# PROFIBUS_V5.net
KiCad netlist of a schematic drawn in EAGLE
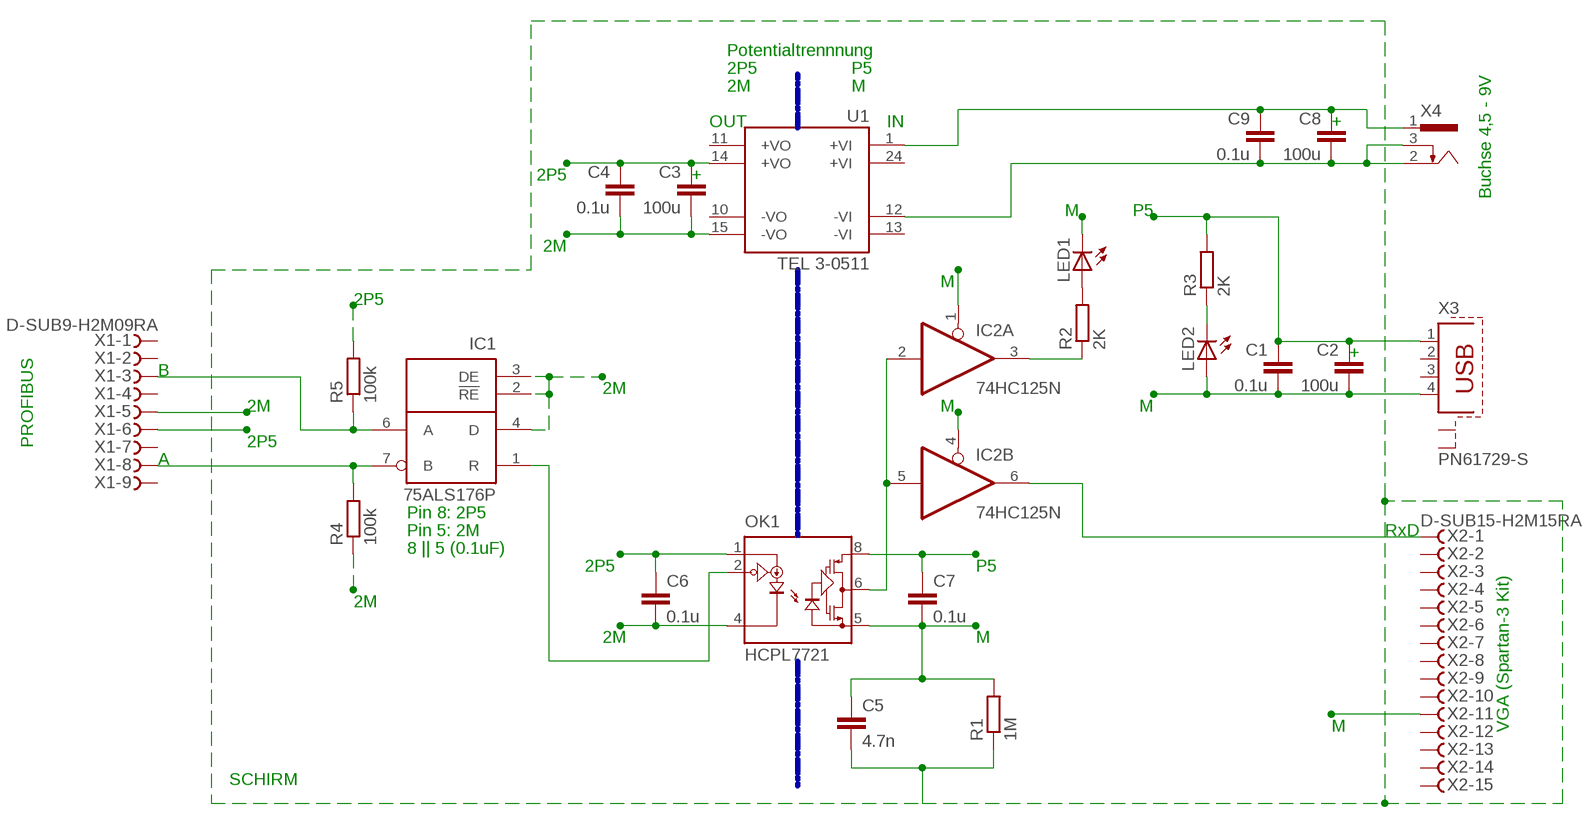
[diagram p0: schematic, sheet 1]

(export (version "E")
  (design (tool "Eeschema 10.0.6"))
  (components
    (comp (ref "C1")
      (value "0.1u")
      (footprint "eagle-import:C2.5-3")
      (libsource (lib "eagle-import") (part "C2,5-3"))
    )
    (comp (ref "C2")
      (value "100u")
      (footprint "eagle-import:C2.5-3")
      (libsource (lib "eagle-import") (part "C2,5-3"))
    )
    (comp (ref "C3")
      (value "100u")
      (footprint "eagle-import:C2.5-3")
      (libsource (lib "eagle-import") (part "C2,5-3"))
    )
    (comp (ref "C4")
      (value "0.1u")
      (footprint "eagle-import:C2.5-3")
      (libsource (lib "eagle-import") (part "C2,5-3"))
    )
    (comp (ref "C5")
      (value "4.7n")
      (footprint "eagle-import:C2.5-3")
      (libsource (lib "eagle-import") (part "C2,5-3"))
    )
    (comp (ref "C6")
      (value "0.1u")
      (footprint "eagle-import:C2.5-3")
      (libsource (lib "eagle-import") (part "C2,5-3"))
    )
    (comp (ref "C7")
      (value "0.1u")
      (footprint "eagle-import:C2.5-3")
      (libsource (lib "eagle-import") (part "C2,5-3"))
    )
    (comp (ref "C8")
      (value "100u")
      (footprint "eagle-import:C2.5-3")
      (libsource (lib "eagle-import") (part "C2,5-3"))
    )
    (comp (ref "C9")
      (value "0.1u")
      (footprint "eagle-import:C2.5-3")
      (libsource (lib "eagle-import") (part "C2,5-3"))
    )
    (comp (ref "IC1")
      (value "75ALS176P")
      (footprint "eagle-import:DIL08")
      (fields (field (name "MF") "TEXAS INSTRUMENTS") (field (name "MPN") "SN75ALS176P"))
      (libsource (lib "eagle-import") (part "75ALS176P"))
    )
    (comp (ref "IC2")
      (value "74HC125N")
      (footprint "eagle-import:DIL14")
      (libsource (lib "eagle-import") (part "74125NHC"))
    )
    (comp (ref "LED1")
      (value "TLLY4400")
      (footprint "eagle-import:LED3MM")
      (fields (field (name "MF") "VISHAY SEMICONDUCTOR"))
      (libsource (lib "eagle-import") (part "TLLY4400"))
    )
    (comp (ref "LED2")
      (value "TLLG4400")
      (footprint "eagle-import:LED3MM")
      (fields (field (name "MF") "VISHAY SEMICONDUCTOR"))
      (libsource (lib "eagle-import") (part "TLLG4400"))
    )
    (comp (ref "OK1")
      (value "HCPL7721")
      (footprint "eagle-import:DIL08")
      (fields (field (name "MF") "AGILENT TECHNOLOGIES") (field (name "MPN") "HCPL-7721"))
      (libsource (lib "eagle-import") (part "HCPL7721"))
    )
    (comp (ref "R1")
      (value "1M")
      (footprint "eagle-import:0204_7")
      (libsource (lib "eagle-import") (part "R-EU_0204/7"))
    )
    (comp (ref "R2")
      (value "2K")
      (footprint "eagle-import:0204_7")
      (libsource (lib "eagle-import") (part "R-EU_0204/7"))
    )
    (comp (ref "R3")
      (value "2K")
      (footprint "eagle-import:0204_7")
      (libsource (lib "eagle-import") (part "R-EU_0204/7"))
    )
    (comp (ref "R4")
      (value "100k")
      (footprint "eagle-import:0204_7")
      (libsource (lib "eagle-import") (part "R-EU_0204/7"))
    )
    (comp (ref "R5")
      (value "100k")
      (footprint "eagle-import:0204_7")
      (libsource (lib "eagle-import") (part "R-EU_0204/7"))
    )
    (comp (ref "U1")
      (value "TEL 3-0511")
      (footprint "eagle-import:AM3N_DIL24")
      (libsource (lib "eagle-import") (part "AM3N-S0505"))
    )
    (comp (ref "X1")
      (value "D-SUB9-H2M09RA")
      (footprint "eagle-import:H2M09RA")
      (libsource (lib "eagle-import") (part "D-SUB9-H2M09RA"))
    )
    (comp (ref "X2")
      (value "D-SUB15-H2M15RA")
      (footprint "eagle-import:H2M15RA")
      (fields (field (name "MPN") "H2M15RA29B"))
      (libsource (lib "eagle-import") (part "D-SUB15-H2M15RA"))
    )
    (comp (ref "X3")
      (value "PN61729-S")
      (footprint "eagle-import:PN61729-S")
      (libsource (lib "eagle-import") (part "PN61729-S"))
    )
    (comp (ref "X4")
      (value "733980-62")
      (footprint "eagle-import:733980-62")
      (libsource (lib "eagle-import") (part "73398?0-62"))
    )
  )
  (nets
    (net (code "1") (name "/+VI") (class "Default")
      (node (ref "U1") (pin "24") (pinfunction "+VI_24") (pintype "power_in"))
    )
    (net (code "2") (name "/+VO") (class "Default")
      (node (ref "U1") (pin "11") (pinfunction "+VO_11") (pintype "power_in"))
    )
    (net (code "3") (name "/-VI") (class "Default")
      (node (ref "U1") (pin "13") (pinfunction "-VI_13") (pintype "power_in"))
    )
    (net (code "4") (name "/-VO") (class "Default")
      (node (ref "U1") (pin "10") (pinfunction "-VO_10") (pintype "power_in"))
    )
    (net (code "5") (name "Net-(C1-Pad1)") (class "Default")
      (node (ref "C1") (pin "1") (pinfunction "1_1") (pintype "passive"))
      (node (ref "C2") (pin "1") (pinfunction "1_1") (pintype "passive"))
      (node (ref "R3") (pin "2") (pinfunction "2_2") (pintype "passive"))
      (node (ref "X3") (pin "1") (pinfunction "1_1") (pintype "passive"))
    )
    (net (code "6") (name "Net-(C1-Pad2)") (class "Default")
      (node (ref "C1") (pin "2") (pinfunction "2_2") (pintype "passive"))
      (node (ref "C2") (pin "2") (pinfunction "2_2") (pintype "passive"))
      (node (ref "LED2") (pin "A") (pinfunction "A_A") (pintype "passive"))
      (node (ref "X3") (pin "4") (pinfunction "4_4") (pintype "passive"))
    )
    (net (code "7") (name "Net-(C3-Pad1)") (class "Default")
      (node (ref "C3") (pin "1") (pinfunction "1_1") (pintype "passive"))
      (node (ref "C4") (pin "1") (pinfunction "1_1") (pintype "passive"))
      (node (ref "U1") (pin "14") (pinfunction "+VO_14") (pintype "power_in"))
    )
    (net (code "8") (name "Net-(C3-Pad2)") (class "Default")
      (node (ref "C3") (pin "2") (pinfunction "2_2") (pintype "passive"))
      (node (ref "C4") (pin "2") (pinfunction "2_2") (pintype "passive"))
      (node (ref "U1") (pin "15") (pinfunction "-VO_15") (pintype "power_in"))
    )
    (net (code "9") (name "Net-(C5-Pad2)") (class "Default")
      (node (ref "C5") (pin "2") (pinfunction "2_2") (pintype "passive"))
      (node (ref "R1") (pin "1") (pinfunction "1_1") (pintype "passive"))
    )
    (net (code "10") (name "Net-(C8-Pad1)") (class "Default")
      (node (ref "C8") (pin "1") (pinfunction "1_1") (pintype "passive"))
      (node (ref "C9") (pin "1") (pinfunction "1_1") (pintype "passive"))
      (node (ref "U1") (pin "1") (pinfunction "+VI_1") (pintype "power_in"))
      (node (ref "X4") (pin "1") (pinfunction "1_1") (pintype "passive"))
    )
    (net (code "11") (name "Net-(C8-Pad2)") (class "Default")
      (node (ref "C8") (pin "2") (pinfunction "2_2") (pintype "passive"))
      (node (ref "C9") (pin "2") (pinfunction "2_2") (pintype "passive"))
      (node (ref "U1") (pin "12") (pinfunction "-VI_12") (pintype "power_in"))
      (node (ref "X4") (pin "2") (pinfunction "2_2") (pintype "passive"))
      (node (ref "X4") (pin "3") (pinfunction "3_3") (pintype "passive"))
    )
    (net (code "12") (name "Net-(IC1A-A)") (class "Default")
      (node (ref "IC1") (pin "6") (pinfunction "A_6") (pintype "bidirectional"))
      (node (ref "R5") (pin "1") (pinfunction "1_1") (pintype "passive"))
      (node (ref "X1") (pin "3") (pinfunction "F_3") (pintype "passive"))
    )
    (net (code "13") (name "Net-(IC1A-B)") (class "Default")
      (node (ref "IC1") (pin "7") (pinfunction "B_7") (pintype "bidirectional"))
      (node (ref "R4") (pin "2") (pinfunction "2_2") (pintype "passive"))
      (node (ref "X1") (pin "8") (pinfunction "F_8") (pintype "passive"))
    )
    (net (code "14") (name "Net-(IC1A-D)") (class "Default")
      (node (ref "IC1") (pin "2") (pinfunction "~{RE}_2") (pintype "input"))
      (node (ref "IC1") (pin "3") (pinfunction "DE_3") (pintype "input"))
      (node (ref "IC1") (pin "4") (pinfunction "D_4") (pintype "input"))
    )
    (net (code "15") (name "Net-(IC1A-R)") (class "Default")
      (node (ref "IC1") (pin "1") (pinfunction "R_1") (pintype "output"))
      (node (ref "OK1") (pin "2") (pinfunction "VI_2") (pintype "input"))
    )
    (net (code "16") (name "Net-(IC2A-I)") (class "Default")
      (node (ref "IC2") (pin "2") (pinfunction "I_2") (pintype "input"))
      (node (ref "IC2") (pin "5") (pinfunction "I_5") (pintype "input"))
      (node (ref "OK1") (pin "6") (pinfunction "VO_6") (pintype "passive"))
    )
    (net (code "17") (name "Net-(IC2A-O)") (class "Default")
      (node (ref "IC2") (pin "3") (pinfunction "O_3") (pintype "tri_state"))
      (node (ref "R2") (pin "1") (pinfunction "1_1") (pintype "passive"))
    )
    (net (code "18") (name "Net-(IC2B-O)") (class "Default")
      (node (ref "IC2") (pin "6") (pinfunction "O_6") (pintype "tri_state"))
      (node (ref "X2") (pin "1") (pinfunction "F_1") (pintype "passive"))
    )
    (net (code "19") (name "Net-(LED1-PadA)") (class "Default")
      (node (ref "LED1") (pin "A") (pinfunction "A_A") (pintype "passive"))
      (node (ref "R2") (pin "2") (pinfunction "2_2") (pintype "passive"))
    )
    (net (code "20") (name "Net-(LED2-C)") (class "Default")
      (node (ref "LED2") (pin "K") (pinfunction "C_K") (pintype "passive"))
      (node (ref "R3") (pin "1") (pinfunction "1_1") (pintype "passive"))
    )
    (net (code "21") (name "Net-(OK1-GND1)") (class "Default")
      (node (ref "C6") (pin "2") (pinfunction "2_2") (pintype "passive"))
      (node (ref "OK1") (pin "4") (pinfunction "GND1_4") (pintype "passive"))
    )
    (net (code "22") (name "Net-(OK1-GND2)") (class "Default")
      (node (ref "C5") (pin "1") (pinfunction "1_1") (pintype "passive"))
      (node (ref "C7") (pin "2") (pinfunction "2_2") (pintype "passive"))
      (node (ref "OK1") (pin "5") (pinfunction "GND2_5") (pintype "passive"))
      (node (ref "R1") (pin "2") (pinfunction "2_2") (pintype "passive"))
    )
    (net (code "23") (name "Net-(OK1-VDD1)") (class "Default")
      (node (ref "C6") (pin "1") (pinfunction "1_1") (pintype "passive"))
      (node (ref "OK1") (pin "1") (pinfunction "VDD1_1") (pintype "passive"))
    )
    (net (code "24") (name "Net-(OK1-VDD2)") (class "Default")
      (node (ref "C7") (pin "1") (pinfunction "1_1") (pintype "passive"))
      (node (ref "OK1") (pin "8") (pinfunction "VDD2_8") (pintype "passive"))
    )
    (net (code "25") (name "unconnected-(IC2A-OE-Pad1)") (class "Default")
      (node (ref "IC2") (pin "1") (pinfunction "OE_1") (pintype "input"))
    )
    (net (code "26") (name "unconnected-(IC2B-OE-Pad4)") (class "Default")
      (node (ref "IC2") (pin "4") (pinfunction "OE_4") (pintype "input"))
    )
    (net (code "27") (name "unconnected-(LED1-C-PadK)") (class "Default")
      (node (ref "LED1") (pin "K") (pinfunction "C_K") (pintype "passive"))
    )
    (net (code "28") (name "unconnected-(R4-Pad1)") (class "Default")
      (node (ref "R4") (pin "1") (pinfunction "1_1") (pintype "passive"))
    )
    (net (code "29") (name "unconnected-(R5-Pad2)") (class "Default")
      (node (ref "R5") (pin "2") (pinfunction "2_2") (pintype "passive"))
    )
    (net (code "30") (name "unconnected-(X1A-F-Pad1)") (class "Default")
      (node (ref "X1") (pin "1") (pinfunction "F_1") (pintype "passive"))
    )
    (net (code "31") (name "unconnected-(X1B-F-Pad2)") (class "Default")
      (node (ref "X1") (pin "2") (pinfunction "F_2") (pintype "passive"))
    )
    (net (code "32") (name "unconnected-(X1D-F-Pad4)") (class "Default")
      (node (ref "X1") (pin "4") (pinfunction "F_4") (pintype "passive"))
    )
    (net (code "33") (name "unconnected-(X1E-F-Pad5)") (class "Default")
      (node (ref "X1") (pin "5") (pinfunction "F_5") (pintype "passive"))
    )
    (net (code "34") (name "unconnected-(X1F-F-Pad6)") (class "Default")
      (node (ref "X1") (pin "6") (pinfunction "F_6") (pintype "passive"))
    )
    (net (code "35") (name "unconnected-(X1G-F-Pad7)") (class "Default")
      (node (ref "X1") (pin "7") (pinfunction "F_7") (pintype "passive"))
    )
    (net (code "36") (name "unconnected-(X1I-F-Pad9)") (class "Default")
      (node (ref "X1") (pin "9") (pinfunction "F_9") (pintype "passive"))
    )
    (net (code "37") (name "unconnected-(X2B-F-Pad10)") (class "Default")
      (node (ref "X2") (pin "10") (pinfunction "F_10") (pintype "passive"))
    )
    (net (code "38") (name "unconnected-(X2C-F-Pad11)") (class "Default")
      (node (ref "X2") (pin "11") (pinfunction "F_11") (pintype "passive"))
    )
    (net (code "39") (name "unconnected-(X2D-F-Pad12)") (class "Default")
      (node (ref "X2") (pin "12") (pinfunction "F_12") (pintype "passive"))
    )
    (net (code "40") (name "unconnected-(X2E-F-Pad13)") (class "Default")
      (node (ref "X2") (pin "13") (pinfunction "F_13") (pintype "passive"))
    )
    (net (code "41") (name "unconnected-(X2F-F-Pad14)") (class "Default")
      (node (ref "X2") (pin "14") (pinfunction "F_14") (pintype "passive"))
    )
    (net (code "42") (name "unconnected-(X2G-F-Pad15)") (class "Default")
      (node (ref "X2") (pin "15") (pinfunction "F_15") (pintype "passive"))
    )
    (net (code "43") (name "unconnected-(X2H-F-Pad2)") (class "Default")
      (node (ref "X2") (pin "2") (pinfunction "F_2") (pintype "passive"))
    )
    (net (code "44") (name "unconnected-(X2I-F-Pad3)") (class "Default")
      (node (ref "X2") (pin "3") (pinfunction "F_3") (pintype "passive"))
    )
    (net (code "45") (name "unconnected-(X2J-F-Pad4)") (class "Default")
      (node (ref "X2") (pin "4") (pinfunction "F_4") (pintype "passive"))
    )
    (net (code "46") (name "unconnected-(X2K-F-Pad5)") (class "Default")
      (node (ref "X2") (pin "5") (pinfunction "F_5") (pintype "passive"))
    )
    (net (code "47") (name "unconnected-(X2L-F-Pad6)") (class "Default")
      (node (ref "X2") (pin "6") (pinfunction "F_6") (pintype "passive"))
    )
    (net (code "48") (name "unconnected-(X2M-F-Pad7)") (class "Default")
      (node (ref "X2") (pin "7") (pinfunction "F_7") (pintype "passive"))
    )
    (net (code "49") (name "unconnected-(X2N-F-Pad8)") (class "Default")
      (node (ref "X2") (pin "8") (pinfunction "F_8") (pintype "passive"))
    )
    (net (code "50") (name "unconnected-(X2O-F-Pad9)") (class "Default")
      (node (ref "X2") (pin "9") (pinfunction "F_9") (pintype "passive"))
    )
    (net (code "51") (name "unconnected-(X3-Pad2)") (class "Default")
      (node (ref "X3") (pin "2") (pinfunction "2_2") (pintype "passive"))
    )
    (net (code "52") (name "unconnected-(X3-Pad3)") (class "Default")
      (node (ref "X3") (pin "3") (pinfunction "3_3") (pintype "passive"))
    )
    (net (code "53") (name "unconnected-(X3-PadS1)") (class "Default")
      (node (ref "X3") (pin "S1") (pinfunction "S1_S1") (pintype "passive"))
    )
    (net (code "54") (name "unconnected-(X3-PadS2)") (class "Default")
      (node (ref "X3") (pin "S2") (pinfunction "S2_S2") (pintype "passive"))
    )
  )
)
